# PDH_TransimpedanceAmp.net
KiCad netlist of a schematic drawn in EAGLE
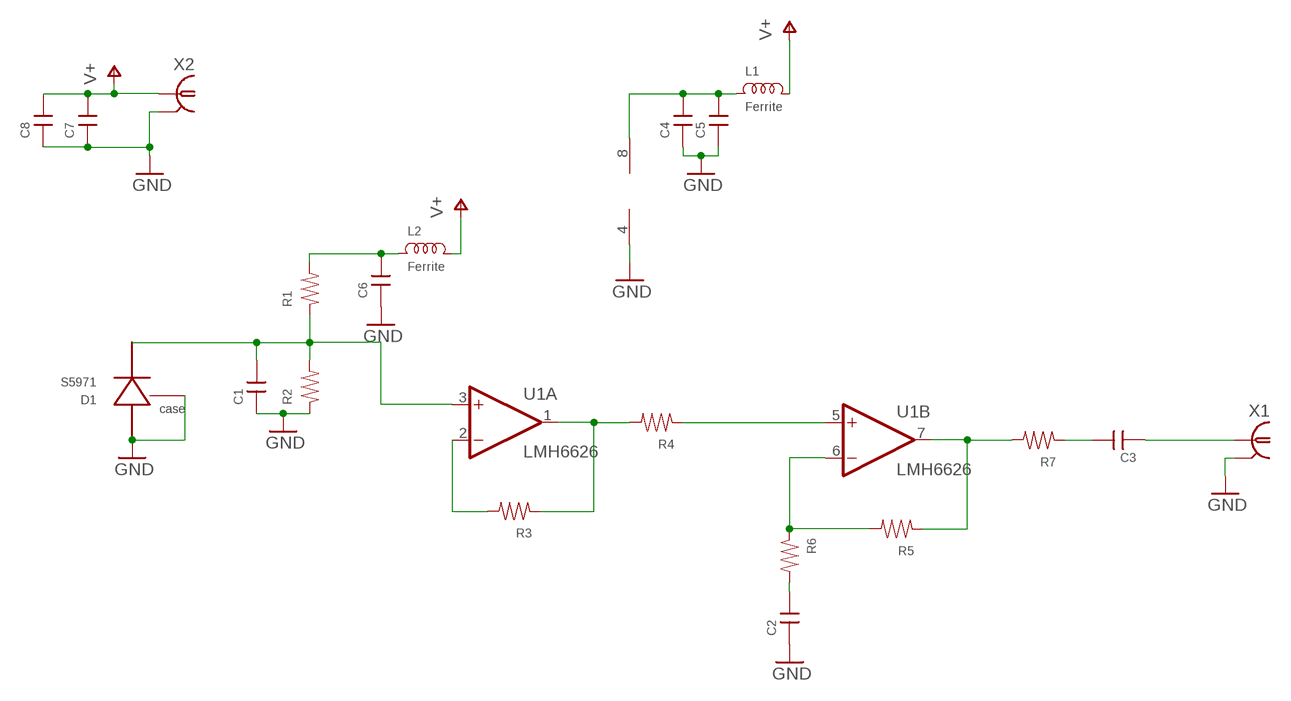
[diagram p0: schematic, sheet 1]

(export (version "E")
  (design (tool "Eeschema 10.0.6"))
  (components
    (comp (ref "C1")
      (value "CAP0402")
      (footprint "eagle-import:0402")
      (libsource (lib "eagle-import") (part "CAP0402"))
    )
    (comp (ref "C2")
      (value "CAP0402")
      (footprint "eagle-import:0402")
      (libsource (lib "eagle-import") (part "CAP0402"))
    )
    (comp (ref "C3")
      (value "CAP0402")
      (footprint "eagle-import:0402")
      (libsource (lib "eagle-import") (part "CAP0402"))
    )
    (comp (ref "C4")
      (value "CAP0402")
      (footprint "eagle-import:0402")
      (libsource (lib "eagle-import") (part "CAP0402"))
    )
    (comp (ref "C5")
      (value "CAP0805")
      (footprint "eagle-import:0805")
      (libsource (lib "eagle-import") (part "CAP0805"))
    )
    (comp (ref "C6")
      (value "CAP0805")
      (footprint "eagle-import:0805")
      (libsource (lib "eagle-import") (part "CAP0805"))
    )
    (comp (ref "C7")
      (value "CAP0805")
      (footprint "eagle-import:0805")
      (libsource (lib "eagle-import") (part "CAP0805"))
    )
    (comp (ref "C8")
      (value "CAP0402")
      (footprint "eagle-import:0402")
      (libsource (lib "eagle-import") (part "CAP0402"))
    )
    (comp (ref "D1")
      (value "S5971")
      (footprint "eagle-import:S5971-CASE")
      (libsource (lib "eagle-import") (part "S5971"))
    )
    (comp (ref "L1")
      (value "Ferrite")
      (footprint "eagle-import:0805")
      (libsource (lib "eagle-import") (part "INDUCTOR-0805"))
    )
    (comp (ref "L2")
      (value "Ferrite")
      (footprint "eagle-import:0805")
      (libsource (lib "eagle-import") (part "INDUCTOR-0805"))
    )
    (comp (ref "R1")
      (value "RES0402")
      (footprint "eagle-import:0402")
      (libsource (lib "eagle-import") (part "RES0402"))
    )
    (comp (ref "R2")
      (value "RES0402")
      (footprint "eagle-import:0402")
      (libsource (lib "eagle-import") (part "RES0402"))
    )
    (comp (ref "R3")
      (value "RES0402")
      (footprint "eagle-import:0402")
      (libsource (lib "eagle-import") (part "RES0402"))
    )
    (comp (ref "R4")
      (value "RES0402")
      (footprint "eagle-import:0402")
      (libsource (lib "eagle-import") (part "RES0402"))
    )
    (comp (ref "R5")
      (value "RES0402")
      (footprint "eagle-import:0402")
      (libsource (lib "eagle-import") (part "RES0402"))
    )
    (comp (ref "R6")
      (value "RES0402")
      (footprint "eagle-import:0402")
      (libsource (lib "eagle-import") (part "RES0402"))
    )
    (comp (ref "R7")
      (value "RES0402")
      (footprint "eagle-import:0402")
      (libsource (lib "eagle-import") (part "RES0402"))
    )
    (comp (ref "U1")
      (value "LMH6626")
      (footprint "eagle-import:SO08")
      (libsource (lib "eagle-import") (part "LMH6626"))
    )
    (comp (ref "X1")
      (value "UMC")
      (footprint "eagle-import:UMC")
      (libsource (lib "eagle-import") (part "UMC"))
    )
    (comp (ref "X2")
      (value "UMC")
      (footprint "eagle-import:UMC")
      (libsource (lib "eagle-import") (part "UMC"))
    )
  )
  (nets
    (net (code "1") (name "GND") (class "Default")
      (node (ref "C1") (pin "1") (pinfunction "P$1_1") (pintype "passive"))
      (node (ref "C2") (pin "1") (pinfunction "P$1_1") (pintype "passive"))
      (node (ref "C4") (pin "1") (pinfunction "P$1_1") (pintype "passive"))
      (node (ref "C5") (pin "1") (pinfunction "P$1_1") (pintype "passive"))
      (node (ref "C6") (pin "1") (pinfunction "P$1_1") (pintype "passive"))
      (node (ref "C7") (pin "1") (pinfunction "P$1_1") (pintype "passive"))
      (node (ref "C8") (pin "1") (pinfunction "P$1_1") (pintype "passive"))
      (node (ref "D1") (pin "P$2") (pinfunction "CASE_P$2") (pintype "bidirectional"))
      (node (ref "D1") (pin "P$3") (pinfunction "ANODE_P$3") (pintype "bidirectional"))
      (node (ref "R2") (pin "1") (pinfunction "P$1_1") (pintype "passive"))
      (node (ref "U1") (pin "4") (pinfunction "V-_4") (pintype "power_in"))
      (node (ref "X1") (pin "P$2") (pinfunction "2_P$2") (pintype "passive"))
      (node (ref "X1") (pin "P$3") (pinfunction "2_P$3") (pintype "passive"))
      (node (ref "X2") (pin "P$2") (pinfunction "2_P$2") (pintype "passive"))
      (node (ref "X2") (pin "P$3") (pinfunction "2_P$3") (pintype "passive"))
    )
    (net (code "2") (name "Net-(C1-P$2)") (class "Default")
      (node (ref "C1") (pin "2") (pinfunction "P$2_2") (pintype "passive"))
      (node (ref "D1") (pin "P$1") (pinfunction "CATHODE_P$1") (pintype "bidirectional"))
      (node (ref "R1") (pin "1") (pinfunction "P$1_1") (pintype "passive"))
      (node (ref "R2") (pin "2") (pinfunction "P$2_2") (pintype "passive"))
      (node (ref "U1") (pin "3") (pinfunction "+IN_3") (pintype "input"))
    )
    (net (code "3") (name "Net-(C2-P$2)") (class "Default")
      (node (ref "C2") (pin "2") (pinfunction "P$2_2") (pintype "passive"))
      (node (ref "R6") (pin "2") (pinfunction "P$2_2") (pintype "passive"))
    )
    (net (code "4") (name "Net-(C3-P$1)") (class "Default")
      (node (ref "C3") (pin "1") (pinfunction "P$1_1") (pintype "passive"))
      (node (ref "X1") (pin "P$1") (pinfunction "1_P$1") (pintype "passive"))
    )
    (net (code "5") (name "Net-(C3-P$2)") (class "Default")
      (node (ref "C3") (pin "2") (pinfunction "P$2_2") (pintype "passive"))
      (node (ref "R7") (pin "1") (pinfunction "P$1_1") (pintype "passive"))
    )
    (net (code "6") (name "Net-(C4-P$2)") (class "Default")
      (node (ref "C4") (pin "2") (pinfunction "P$2_2") (pintype "passive"))
      (node (ref "C5") (pin "2") (pinfunction "P$2_2") (pintype "passive"))
      (node (ref "L1") (pin "1") (pinfunction "P$1_1") (pintype "passive"))
      (node (ref "U1") (pin "8") (pinfunction "V+_8") (pintype "power_in"))
    )
    (net (code "7") (name "Net-(C6-P$2)") (class "Default")
      (node (ref "C6") (pin "2") (pinfunction "P$2_2") (pintype "passive"))
      (node (ref "L2") (pin "1") (pinfunction "P$1_1") (pintype "passive"))
      (node (ref "R1") (pin "2") (pinfunction "P$2_2") (pintype "passive"))
    )
    (net (code "8") (name "Net-(R3-P$1)") (class "Default")
      (node (ref "R3") (pin "1") (pinfunction "P$1_1") (pintype "passive"))
      (node (ref "R4") (pin "2") (pinfunction "P$2_2") (pintype "passive"))
      (node (ref "U1") (pin "1") (pinfunction "OUT_1") (pintype "output"))
    )
    (net (code "9") (name "Net-(R3-P$2)") (class "Default")
      (node (ref "R3") (pin "2") (pinfunction "P$2_2") (pintype "passive"))
      (node (ref "U1") (pin "2") (pinfunction "-IN_2") (pintype "input"))
    )
    (net (code "10") (name "Net-(R4-P$1)") (class "Default")
      (node (ref "R4") (pin "1") (pinfunction "P$1_1") (pintype "passive"))
      (node (ref "U1") (pin "5") (pinfunction "+IN_5") (pintype "input"))
    )
    (net (code "11") (name "Net-(R5-P$1)") (class "Default")
      (node (ref "R5") (pin "1") (pinfunction "P$1_1") (pintype "passive"))
      (node (ref "R7") (pin "2") (pinfunction "P$2_2") (pintype "passive"))
      (node (ref "U1") (pin "7") (pinfunction "OUT_7") (pintype "output"))
    )
    (net (code "12") (name "Net-(R5-P$2)") (class "Default")
      (node (ref "R5") (pin "2") (pinfunction "P$2_2") (pintype "passive"))
      (node (ref "R6") (pin "1") (pinfunction "P$1_1") (pintype "passive"))
      (node (ref "U1") (pin "6") (pinfunction "-IN_6") (pintype "input"))
    )
    (net (code "13") (name "V+") (class "Default")
      (node (ref "C7") (pin "2") (pinfunction "P$2_2") (pintype "passive"))
      (node (ref "C8") (pin "2") (pinfunction "P$2_2") (pintype "passive"))
      (node (ref "L1") (pin "2") (pinfunction "P$2_2") (pintype "passive"))
      (node (ref "L2") (pin "2") (pinfunction "P$2_2") (pintype "passive"))
      (node (ref "X2") (pin "P$1") (pinfunction "1_P$1") (pintype "passive"))
    )
  )
)
